# atmega32u4bb.net
KiCad netlist of a schematic drawn in EAGLE
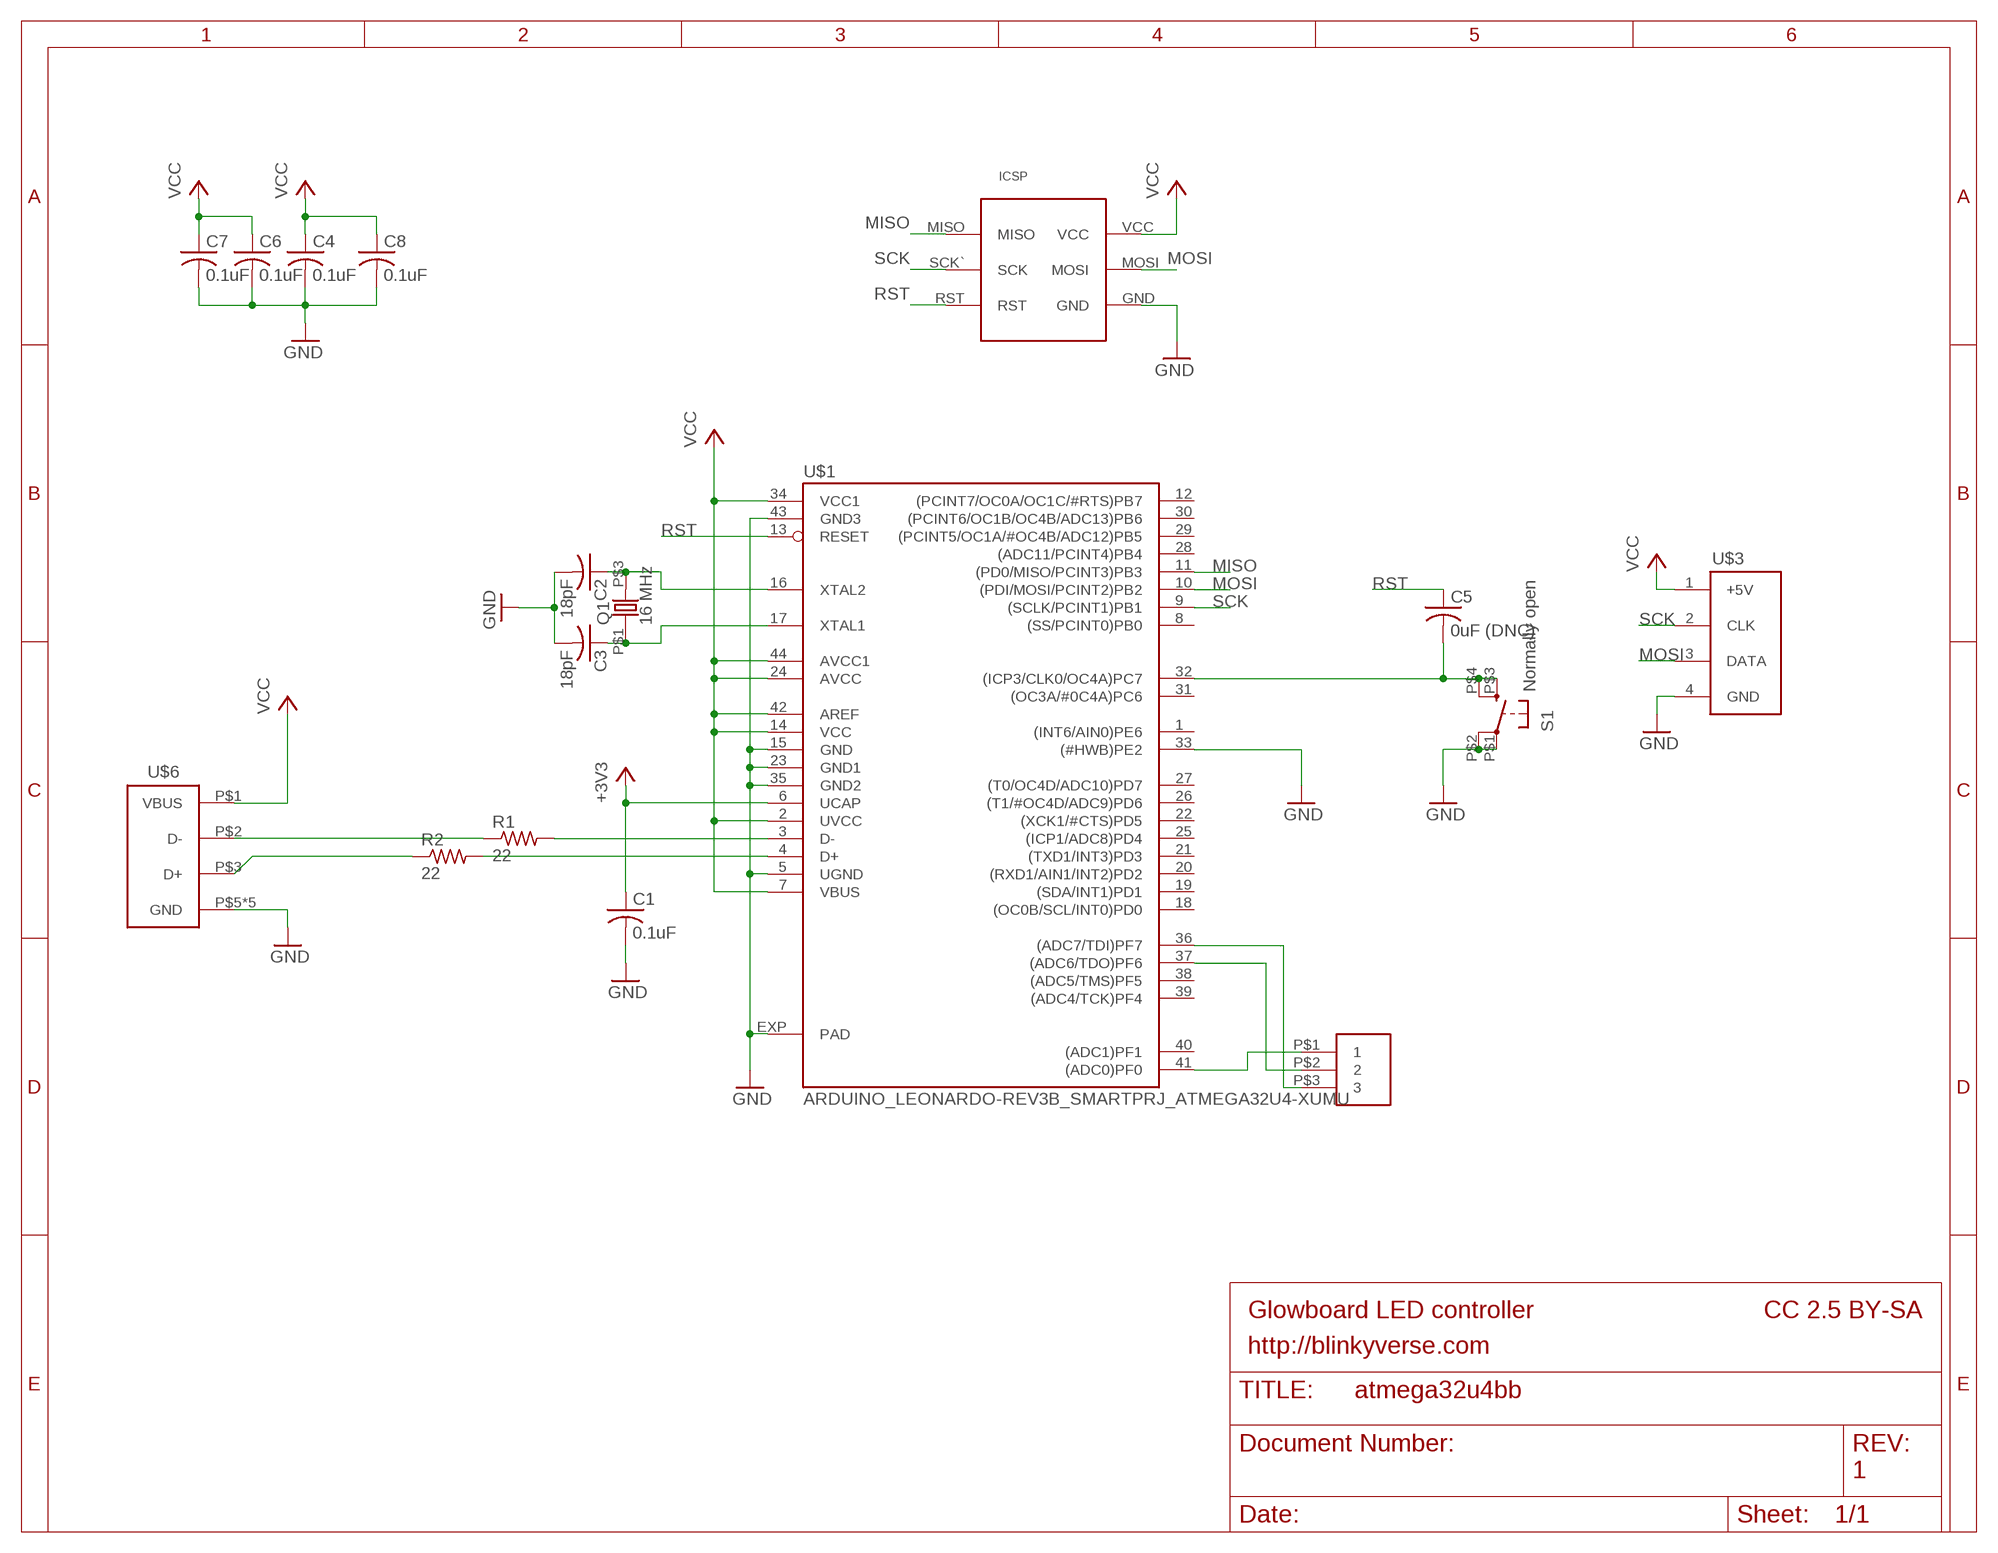
[diagram p0: schematic, sheet 1]

(export (version "E")
  (design (tool "Eeschema 10.0.6"))
  (components
    (comp (ref "C1")
      (value "0.1uF")
      (footprint "eagle-import:C0805K")
      (libsource (lib "eagle-import") (part "C-USC0805K"))
    )
    (comp (ref "C2")
      (value "18pF")
      (footprint "eagle-import:C0805K")
      (libsource (lib "eagle-import") (part "C-USC0805K"))
    )
    (comp (ref "C3")
      (value "18pF")
      (footprint "eagle-import:C0805K")
      (libsource (lib "eagle-import") (part "C-USC0805K"))
    )
    (comp (ref "C4")
      (value "0.1uF")
      (footprint "eagle-import:C0805K")
      (libsource (lib "eagle-import") (part "C-USC0805K"))
    )
    (comp (ref "C5")
      (value "0uF (DNC)")
      (footprint "eagle-import:C0805K")
      (libsource (lib "eagle-import") (part "C-USC0805K"))
    )
    (comp (ref "C6")
      (value "0.1uF")
      (footprint "eagle-import:C0805K")
      (libsource (lib "eagle-import") (part "C-USC0805K"))
    )
    (comp (ref "C7")
      (value "0.1uF")
      (footprint "eagle-import:C0805K")
      (libsource (lib "eagle-import") (part "C-USC0805K"))
    )
    (comp (ref "C8")
      (value "0.1uF")
      (footprint "eagle-import:C0805K")
      (libsource (lib "eagle-import") (part "C-USC0805K"))
    )
    (comp (ref "Q1")
      (value "16 MHz")
      (footprint "eagle-import:ABMM2_CRYSTAL")
      (libsource (lib "eagle-import") (part "ABMM2"))
    )
    (comp (ref "R1")
      (value "22")
      (footprint "eagle-import:R0805")
      (libsource (lib "eagle-import") (part "R-US_R0805"))
    )
    (comp (ref "R2")
      (value "22")
      (footprint "eagle-import:R0805")
      (libsource (lib "eagle-import") (part "R-US_R0805"))
    )
    (comp (ref "S1")
      (value "Normally open")
      (footprint "eagle-import:GLOWBOARD_KMR211G_SWITCH")
      (libsource (lib "eagle-import") (part "GLOWBOARD_KMR211G"))
    )
    (comp (ref "U$1")
      (value "ARDUINO_LEONARDO-REV3B_SMARTPRJ_ATMEGA32U4-XUMU")
      (footprint "eagle-import:ARDUINO_LEONARDO-REV3B_SMARTPRJ_QFN44ML7X7")
      (libsource (lib "eagle-import") (part "ARDUINO_LEONARDO-REV3B_SMARTPRJ_ATMEGA32U4-XUMU"))
    )
    (comp (ref "U$3")
      (value "GLOWBOARD_PAD_CONNECTION")
      (footprint "eagle-import:GLOWBOARD_PAD_CONNECTION")
      (libsource (lib "eagle-import") (part "GLOWBOARD_PAD_CONNECTION"))
    )
    (comp (ref "U$4")
      (value "GLOWBOARD_ICSP")
      (footprint "eagle-import:GLOWBOARD_ICSP_PADS")
      (libsource (lib "eagle-import") (part "GLOWBOARD_ICSP"))
    )
    (comp (ref "U$5")
      (value "GLOWBOARD_EXPANSION_HEADER")
      (footprint "eagle-import:GLOWBOARD_EXPANSION_HEADER")
      (libsource (lib "eagle-import") (part "GLOWBOARD_EXPANSION_HEADER"))
    )
    (comp (ref "U$6")
      (value "GLOWBOARD_MINI_USB")
      (footprint "eagle-import:GLOWBOARD_MINI_USB_PADS")
      (libsource (lib "eagle-import") (part "GLOWBOARD_MINI_USB"))
    )
  )
  (nets
    (net (code "1") (name "+3V3") (class "Default")
      (node (ref "C1") (pin "1") (pinfunction "1_1") (pintype "passive"))
      (node (ref "U$1") (pin "6") (pinfunction "UCAP_6") (pintype "passive"))
    )
    (net (code "2") (name "/MISO") (class "Default")
      (node (ref "U$1") (pin "11") (pinfunction "(PD0/MISO/PCINT3)PB3_11") (pintype "bidirectional"))
      (node (ref "U$4") (pin "MISO") (pinfunction "MISO_MISO") (pintype "bidirectional"))
    )
    (net (code "3") (name "/MOSI") (class "Default")
      (node (ref "U$1") (pin "10") (pinfunction "(PDI/MOSI/PCINT2)PB2_10") (pintype "bidirectional"))
      (node (ref "U$3") (pin "3") (pinfunction "DATA_3") (pintype "bidirectional"))
      (node (ref "U$4") (pin "MOSI") (pinfunction "MOSI_MOSI") (pintype "bidirectional"))
    )
    (net (code "4") (name "/RST") (class "Default")
      (node (ref "C5") (pin "1") (pinfunction "1_1") (pintype "passive"))
      (node (ref "U$1") (pin "13") (pinfunction "RESET_13") (pintype "input"))
      (node (ref "U$4") (pin "RST") (pinfunction "RST_RST") (pintype "bidirectional"))
    )
    (net (code "5") (name "/SCK") (class "Default")
      (node (ref "U$1") (pin "9") (pinfunction "(SCLK/PCINT1)PB1_9") (pintype "bidirectional"))
      (node (ref "U$3") (pin "2") (pinfunction "CLK_2") (pintype "bidirectional"))
      (node (ref "U$4") (pin "SCK`") (pinfunction "SCK_SCK`") (pintype "bidirectional"))
    )
    (net (code "6") (name "GND") (class "Default")
      (node (ref "C1") (pin "2") (pinfunction "2_2") (pintype "passive"))
      (node (ref "C2") (pin "2") (pinfunction "2_2") (pintype "passive"))
      (node (ref "C3") (pin "2") (pinfunction "2_2") (pintype "passive"))
      (node (ref "C4") (pin "2") (pinfunction "2_2") (pintype "passive"))
      (node (ref "C6") (pin "2") (pinfunction "2_2") (pintype "passive"))
      (node (ref "C7") (pin "2") (pinfunction "2_2") (pintype "passive"))
      (node (ref "C8") (pin "2") (pinfunction "2_2") (pintype "passive"))
      (node (ref "S1") (pin "P$1") (pinfunction "P_P$1") (pintype "passive"))
      (node (ref "S1") (pin "P$2") (pinfunction "P1_P$2") (pintype "passive"))
      (node (ref "U$1") (pin "15") (pinfunction "GND_15") (pintype "power_in"))
      (node (ref "U$1") (pin "23") (pinfunction "GND1_23") (pintype "power_in"))
      (node (ref "U$1") (pin "33") (pinfunction "(#HWB)PE2_33") (pintype "bidirectional"))
      (node (ref "U$1") (pin "35") (pinfunction "GND2_35") (pintype "power_in"))
      (node (ref "U$1") (pin "43") (pinfunction "GND3_43") (pintype "power_in"))
      (node (ref "U$1") (pin "5") (pinfunction "UGND_5") (pintype "power_in"))
      (node (ref "U$1") (pin "EXP") (pinfunction "PAD_EXP") (pintype "power_in"))
      (node (ref "U$3") (pin "4") (pinfunction "GND_4") (pintype "bidirectional"))
      (node (ref "U$4") (pin "GND") (pinfunction "GND_GND") (pintype "bidirectional"))
      (node (ref "U$6") (pin "P$5") (pinfunction "GND_P$5") (pintype "bidirectional"))
      (node (ref "U$6") (pin "P$6") (pinfunction "GND_P$6") (pintype "bidirectional"))
      (node (ref "U$6") (pin "P$7") (pinfunction "GND_P$7") (pintype "bidirectional"))
      (node (ref "U$6") (pin "P$8") (pinfunction "GND_P$8") (pintype "bidirectional"))
      (node (ref "U$6") (pin "P$9") (pinfunction "GND_P$9") (pintype "bidirectional"))
    )
    (net (code "7") (name "Net-(Q1-1)") (class "Default")
      (node (ref "C3") (pin "1") (pinfunction "1_1") (pintype "passive"))
      (node (ref "Q1") (pin "P$1") (pinfunction "1_P$1") (pintype "passive"))
      (node (ref "U$1") (pin "17") (pinfunction "XTAL1_17") (pintype "bidirectional"))
    )
    (net (code "8") (name "Net-(Q1-2)") (class "Default")
      (node (ref "C2") (pin "1") (pinfunction "1_1") (pintype "passive"))
      (node (ref "Q1") (pin "P$3") (pinfunction "2_P$3") (pintype "passive"))
      (node (ref "U$1") (pin "16") (pinfunction "XTAL2_16") (pintype "bidirectional"))
    )
    (net (code "9") (name "Net-(S1-S)") (class "Default")
      (node (ref "C5") (pin "2") (pinfunction "2_2") (pintype "passive"))
      (node (ref "S1") (pin "P$3") (pinfunction "S_P$3") (pintype "passive"))
      (node (ref "S1") (pin "P$4") (pinfunction "S1_P$4") (pintype "passive"))
      (node (ref "U$1") (pin "32") (pinfunction "(ICP3/CLK0/OC4A)PC7_32") (pintype "bidirectional"))
    )
    (net (code "10") (name "Net-(U$1-(ADC0)PF0)") (class "Default")
      (node (ref "U$1") (pin "41") (pinfunction "(ADC0)PF0_41") (pintype "bidirectional"))
      (node (ref "U$5") (pin "P$1") (pinfunction "1_P$1") (pintype "bidirectional"))
    )
    (net (code "11") (name "Net-(U$1-(ADC6{slash}TDO)PF6)") (class "Default")
      (node (ref "U$1") (pin "37") (pinfunction "(ADC6/TDO)PF6_37") (pintype "bidirectional"))
      (node (ref "U$5") (pin "P$2") (pinfunction "2_P$2") (pintype "bidirectional"))
    )
    (net (code "12") (name "Net-(U$1-(ADC7{slash}TDI)PF7)") (class "Default")
      (node (ref "U$1") (pin "36") (pinfunction "(ADC7/TDI)PF7_36") (pintype "bidirectional"))
      (node (ref "U$5") (pin "P$3") (pinfunction "3_P$3") (pintype "bidirectional"))
    )
    (net (code "13") (name "Net-(U$1-D+)") (class "Default")
      (node (ref "R2") (pin "2") (pinfunction "2_2") (pintype "passive"))
      (node (ref "U$1") (pin "4") (pinfunction "D+_4") (pintype "bidirectional"))
    )
    (net (code "14") (name "Net-(U$1-D-)") (class "Default")
      (node (ref "R1") (pin "2") (pinfunction "2_2") (pintype "passive"))
      (node (ref "U$1") (pin "3") (pinfunction "D-_3") (pintype "bidirectional"))
    )
    (net (code "15") (name "Net-(U$6-D+)") (class "Default")
      (node (ref "R2") (pin "1") (pinfunction "1_1") (pintype "passive"))
      (node (ref "U$6") (pin "P$3") (pinfunction "D+_P$3") (pintype "bidirectional"))
    )
    (net (code "16") (name "Net-(U$6-D-)") (class "Default")
      (node (ref "R1") (pin "1") (pinfunction "1_1") (pintype "passive"))
      (node (ref "U$6") (pin "P$2") (pinfunction "D-_P$2") (pintype "bidirectional"))
    )
    (net (code "17") (name "VCC") (class "Default")
      (node (ref "C4") (pin "1") (pinfunction "1_1") (pintype "passive"))
      (node (ref "C6") (pin "1") (pinfunction "1_1") (pintype "passive"))
      (node (ref "C7") (pin "1") (pinfunction "1_1") (pintype "passive"))
      (node (ref "C8") (pin "1") (pinfunction "1_1") (pintype "passive"))
      (node (ref "U$1") (pin "14") (pinfunction "VCC_14") (pintype "power_in"))
      (node (ref "U$1") (pin "2") (pinfunction "UVCC_2") (pintype "power_in"))
      (node (ref "U$1") (pin "24") (pinfunction "AVCC_24") (pintype "power_in"))
      (node (ref "U$1") (pin "34") (pinfunction "VCC1_34") (pintype "power_in"))
      (node (ref "U$1") (pin "42") (pinfunction "AREF_42") (pintype "power_in"))
      (node (ref "U$1") (pin "44") (pinfunction "AVCC1_44") (pintype "power_in"))
      (node (ref "U$1") (pin "7") (pinfunction "VBUS_7") (pintype "input"))
      (node (ref "U$3") (pin "1") (pinfunction "+5V_1") (pintype "bidirectional"))
      (node (ref "U$4") (pin "VCC") (pinfunction "VCC_VCC") (pintype "bidirectional"))
      (node (ref "U$6") (pin "P$1") (pinfunction "VBUS_P$1") (pintype "bidirectional"))
    )
    (net (code "18") (name "unconnected-(U$1-(ADC1)PF1-Pad40)") (class "Default")
      (node (ref "U$1") (pin "40") (pinfunction "(ADC1)PF1_40") (pintype "bidirectional"))
    )
    (net (code "19") (name "unconnected-(U$1-(ADC4{slash}TCK)PF4-Pad39)") (class "Default")
      (node (ref "U$1") (pin "39") (pinfunction "(ADC4/TCK)PF4_39") (pintype "bidirectional"))
    )
    (net (code "20") (name "unconnected-(U$1-(ADC5{slash}TMS)PF5-Pad38)") (class "Default")
      (node (ref "U$1") (pin "38") (pinfunction "(ADC5/TMS)PF5_38") (pintype "bidirectional"))
    )
    (net (code "21") (name "unconnected-(U$1-(ADC11{slash}PCINT4)PB4-Pad28)") (class "Default")
      (node (ref "U$1") (pin "28") (pinfunction "(ADC11/PCINT4)PB4_28") (pintype "bidirectional"))
    )
    (net (code "22") (name "unconnected-(U$1-(ICP1{slash}ADC8)PD4-Pad25)") (class "Default")
      (node (ref "U$1") (pin "25") (pinfunction "(ICP1/ADC8)PD4_25") (pintype "bidirectional"))
    )
    (net (code "23") (name "unconnected-(U$1-(INT6{slash}AIN0)PE6-Pad1)") (class "Default")
      (node (ref "U$1") (pin "1") (pinfunction "(INT6/AIN0)PE6_1") (pintype "bidirectional"))
    )
    (net (code "24") (name "unconnected-(U$1-(OC0B{slash}SCL{slash}INT0)PD0-Pad18)") (class "Default")
      (node (ref "U$1") (pin "18") (pinfunction "(OC0B/SCL/INT0)PD0_18") (pintype "bidirectional"))
    )
    (net (code "25") (name "unconnected-(U$1-(OC3A{slash}#0C4A)PC6-Pad31)") (class "Default")
      (node (ref "U$1") (pin "31") (pinfunction "(OC3A/#0C4A)PC6_31") (pintype "bidirectional"))
    )
    (net (code "26") (name "unconnected-(U$1-(PCINT5{slash}OC1A{slash}#OC4B{slash}ADC12)PB5-Pad29)") (class "Default")
      (node (ref "U$1") (pin "29") (pinfunction "(PCINT5/OC1A/#OC4B/ADC12)PB5_29") (pintype "bidirectional"))
    )
    (net (code "27") (name "unconnected-(U$1-(PCINT6{slash}OC1B{slash}OC4B{slash}ADC13)PB6-Pad30)") (class "Default")
      (node (ref "U$1") (pin "30") (pinfunction "(PCINT6/OC1B/OC4B/ADC13)PB6_30") (pintype "bidirectional"))
    )
    (net (code "28") (name "unconnected-(U$1-(PCINT7{slash}OC0A{slash}OC1C{slash}#RTS)PB7-Pad12)") (class "Default")
      (node (ref "U$1") (pin "12") (pinfunction "(PCINT7/OC0A/OC1C/#RTS)PB7_12") (pintype "bidirectional"))
    )
    (net (code "29") (name "unconnected-(U$1-(RXD1{slash}AIN1{slash}INT2)PD2-Pad20)") (class "Default")
      (node (ref "U$1") (pin "20") (pinfunction "(RXD1/AIN1/INT2)PD2_20") (pintype "bidirectional"))
    )
    (net (code "30") (name "unconnected-(U$1-(SDA{slash}INT1)PD1-Pad19)") (class "Default")
      (node (ref "U$1") (pin "19") (pinfunction "(SDA/INT1)PD1_19") (pintype "bidirectional"))
    )
    (net (code "31") (name "unconnected-(U$1-(SS{slash}PCINT0)PB0-Pad8)") (class "Default")
      (node (ref "U$1") (pin "8") (pinfunction "(SS/PCINT0)PB0_8") (pintype "bidirectional"))
    )
    (net (code "32") (name "unconnected-(U$1-(T0{slash}OC4D{slash}ADC10)PD7-Pad27)") (class "Default")
      (node (ref "U$1") (pin "27") (pinfunction "(T0/OC4D/ADC10)PD7_27") (pintype "bidirectional"))
    )
    (net (code "33") (name "unconnected-(U$1-(T1{slash}#OC4D{slash}ADC9)PD6-Pad26)") (class "Default")
      (node (ref "U$1") (pin "26") (pinfunction "(T1/#OC4D/ADC9)PD6_26") (pintype "bidirectional"))
    )
    (net (code "34") (name "unconnected-(U$1-(TXD1{slash}INT3)PD3-Pad21)") (class "Default")
      (node (ref "U$1") (pin "21") (pinfunction "(TXD1/INT3)PD3_21") (pintype "bidirectional"))
    )
    (net (code "35") (name "unconnected-(U$1-(XCK1{slash}#CTS)PD5-Pad22)") (class "Default")
      (node (ref "U$1") (pin "22") (pinfunction "(XCK1/#CTS)PD5_22") (pintype "bidirectional"))
    )
  )
)
